# CutMonitor_Motor.net
KiCad netlist of a schematic drawn in Altium Designer
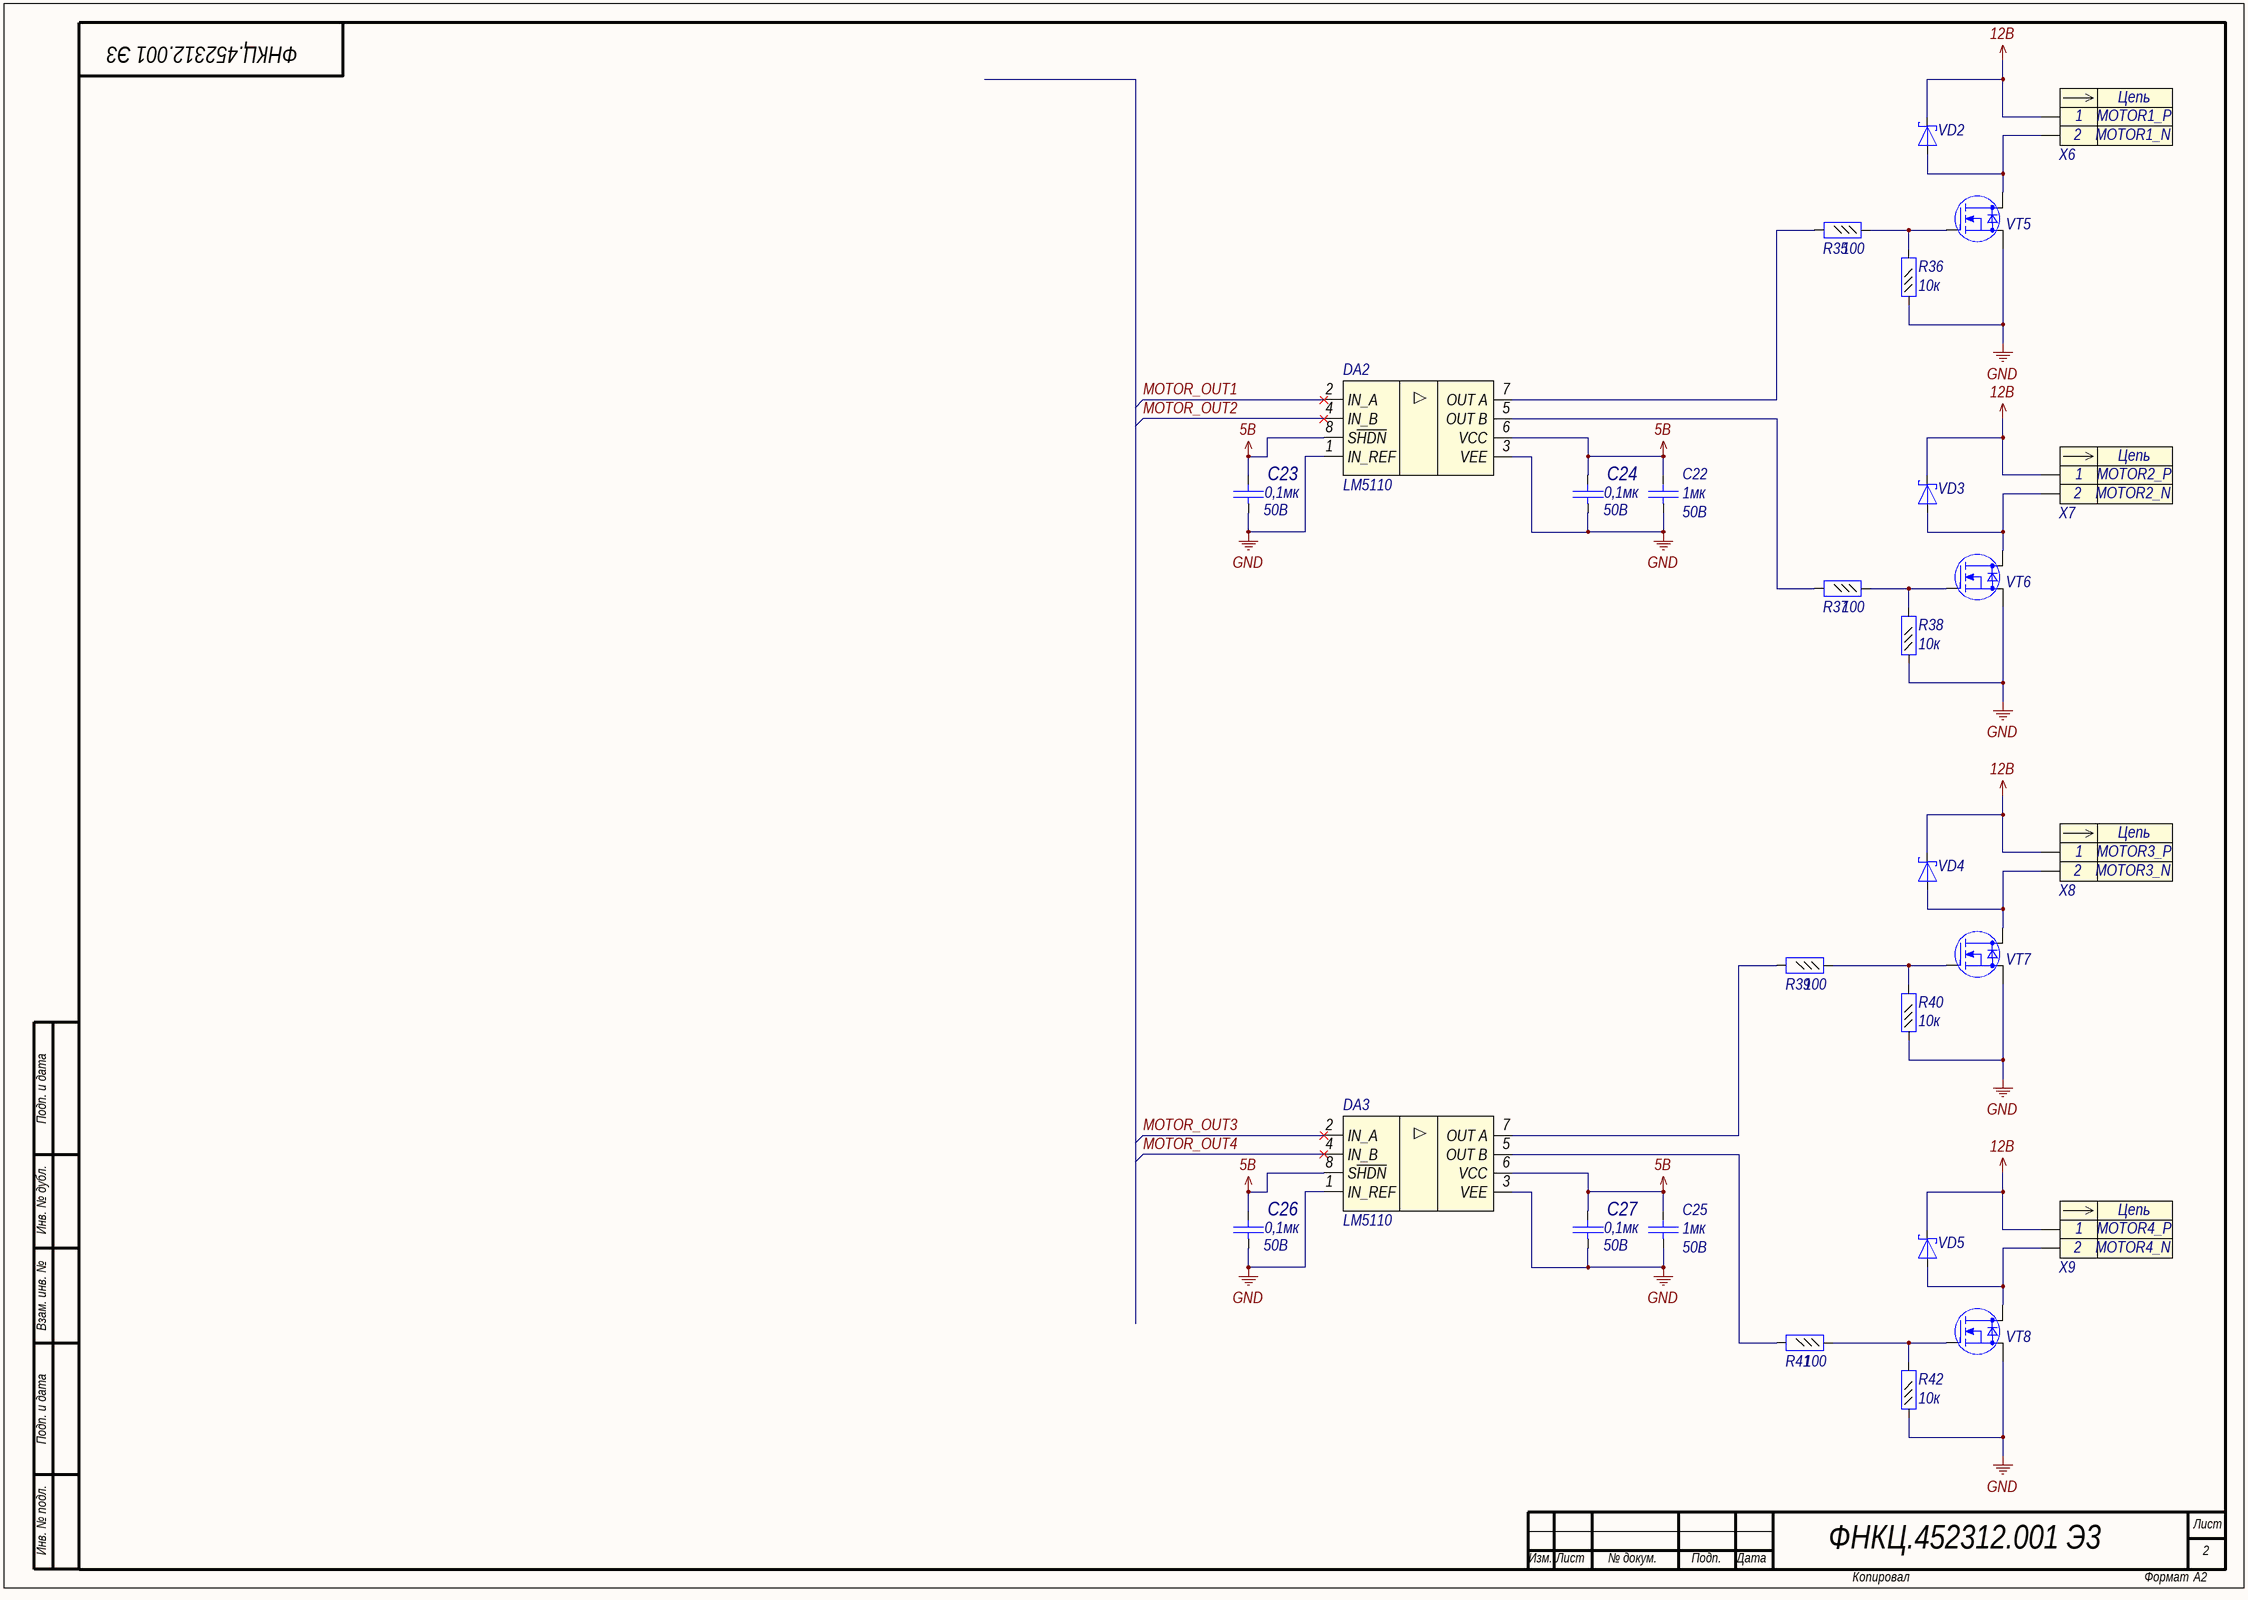
[diagram p0: CutMonitor_Motor.SchDoc]

(export (version "E")
  (design (tool "Eeschema 10.0.6"))
  (components
    (comp (ref "C22")
      (value "1мк")
      (footprint "C0805")
      (description "Конденсатор")
      (fields
        (field (name "VOLTAGE") "50B")
        (field (name "PART NUMBER") "GRM21BR71H105K")
        (field (name "Comment") "Capacitor")
      )
      (libsource (lib "MOP44") (part "Capacitor"))
    )
    (comp (ref "C23")
      (value "0,1мк")
      (footprint "C0603")
      (description "Конденсатор")
      (fields
        (field (name "VOLTAGE") "50B")
        (field (name "PART NUMBER") "GRM188R71H104KA93D")
        (field (name "Comment") "Capacitor")
      )
      (libsource (lib "MOP44") (part "Capacitor"))
    )
    (comp (ref "C24")
      (value "0,1мк")
      (footprint "C0603")
      (description "Конденсатор")
      (fields
        (field (name "VOLTAGE") "50B")
        (field (name "PART NUMBER") "GRM188R71H104KA93D")
        (field (name "Comment") "Capacitor")
      )
      (libsource (lib "MOP44") (part "Capacitor"))
    )
    (comp (ref "C25")
      (value "1мк")
      (footprint "C0805")
      (description "Конденсатор")
      (fields
        (field (name "VOLTAGE") "50B")
        (field (name "PART NUMBER") "GRM21BR71H105K")
        (field (name "Comment") "Capacitor")
      )
      (libsource (lib "MOP44") (part "Capacitor"))
    )
    (comp (ref "C26")
      (value "0,1мк")
      (footprint "C0603")
      (description "Конденсатор")
      (fields
        (field (name "VOLTAGE") "50B")
        (field (name "PART NUMBER") "GRM188R71H104KA93D")
        (field (name "Comment") "Capacitor")
      )
      (libsource (lib "MOP44") (part "Capacitor"))
    )
    (comp (ref "C27")
      (value "0,1мк")
      (footprint "C0603")
      (description "Конденсатор")
      (fields
        (field (name "VOLTAGE") "50B")
        (field (name "PART NUMBER") "GRM188R71H104KA93D")
        (field (name "Comment") "Capacitor")
      )
      (libsource (lib "MOP44") (part "Capacitor"))
    )
    (comp (ref "DA2")
      (value "LM5110")
      (footprint "SO8")
      (description "Driver 5A 2-OUT Low Side Inv/Non-Inv")
      (fields (field (name "PART NUMBER") "LM5110-1M"))
      (libsource (lib "MOP44") (part "LM5110"))
    )
    (comp (ref "DA3")
      (value "LM5110")
      (footprint "SO8")
      (description "Driver 5A 2-OUT Low Side Inv/Non-Inv")
      (fields (field (name "PART NUMBER") "LM5110-1M"))
      (libsource (lib "MOP44") (part "LM5110"))
    )
    (comp (ref "R35")
      (value "100")
      (footprint "R0603")
      (description "Резистор")
      (fields (field (name "PART NUMBER") "RC0603FR-07100RL") (field (name "POWER") "0,062Вт"))
      (libsource (lib "MOP44") (part "Resistor_0,062Вт"))
    )
    (comp (ref "R36")
      (value "10к")
      (footprint "R0603")
      (description "Резистор")
      (fields (field (name "PART NUMBER") "RC0603FR-0710KL") (field (name "POWER") "0,062Вт"))
      (libsource (lib "") (part "Resistor_0,062Вт_1"))
    )
    (comp (ref "R37")
      (value "100")
      (footprint "R0603")
      (description "Резистор")
      (fields (field (name "PART NUMBER") "RC0603FR-07100RL") (field (name "POWER") "0,062Вт"))
      (libsource (lib "MOP44") (part "Resistor_0,062Вт"))
    )
    (comp (ref "R38")
      (value "10к")
      (footprint "R0603")
      (description "Резистор")
      (fields (field (name "PART NUMBER") "RC0603FR-0710KL") (field (name "POWER") "0,062Вт"))
      (libsource (lib "") (part "Resistor_0,062Вт_1"))
    )
    (comp (ref "R39")
      (value "100")
      (footprint "R0603")
      (description "Резистор")
      (fields (field (name "PART NUMBER") "RC0603FR-07100RL") (field (name "POWER") "0,062Вт"))
      (libsource (lib "MOP44") (part "Resistor_0,062Вт"))
    )
    (comp (ref "R40")
      (value "10к")
      (footprint "R0603")
      (description "Резистор")
      (fields (field (name "PART NUMBER") "RC0603FR-0710KL") (field (name "POWER") "0,062Вт"))
      (libsource (lib "") (part "Resistor_0,062Вт_1"))
    )
    (comp (ref "R41")
      (value "100")
      (footprint "R0603")
      (description "Резистор")
      (fields (field (name "PART NUMBER") "RC0603FR-07100RL") (field (name "POWER") "0,062Вт"))
      (libsource (lib "MOP44") (part "Resistor_0,062Вт"))
    )
    (comp (ref "R42")
      (value "10к")
      (footprint "R0603")
      (description "Резистор")
      (fields (field (name "PART NUMBER") "RC0603FR-0710KL") (field (name "POWER") "0,062Вт"))
      (libsource (lib "") (part "Resistor_0,062Вт_1"))
    )
    (comp (ref "VD2")
      (value "DiodeSchottky")
      (footprint "SOD-323")
      (description "Диод Шоттки")
      (fields (field (name "PART NUMBER") "PMEG4010BEA.115"))
      (libsource (lib "MOP44") (part "DiodeSchottky"))
    )
    (comp (ref "VD3")
      (value "DiodeSchottky")
      (footprint "SOD-323")
      (description "Диод Шоттки")
      (fields (field (name "PART NUMBER") "PMEG4010BEA.115"))
      (libsource (lib "MOP44") (part "DiodeSchottky"))
    )
    (comp (ref "VD4")
      (value "DiodeSchottky")
      (footprint "SOD-323")
      (description "Диод Шоттки")
      (fields (field (name "PART NUMBER") "PMEG4010BEA.115"))
      (libsource (lib "MOP44") (part "DiodeSchottky"))
    )
    (comp (ref "VD5")
      (value "DiodeSchottky")
      (footprint "SOD-323")
      (description "Диод Шоттки")
      (fields (field (name "PART NUMBER") "PMEG4010BEA.115"))
      (libsource (lib "MOP44") (part "DiodeSchottky"))
    )
    (comp (ref "VT5")
      (value "N-MOSFET")
      (footprint "DPAK")
      (fields
        (field (name "PART NUMBER") "IRLR2905ZPBF")
        (field (name "MANUFACTURER") "International Rectifier")
      )
      (libsource (lib "MOP44") (part "N-MOSFET"))
    )
    (comp (ref "VT6")
      (value "N-MOSFET")
      (footprint "DPAK")
      (fields
        (field (name "PART NUMBER") "IRLR2905ZPBF")
        (field (name "MANUFACTURER") "International Rectifier")
      )
      (libsource (lib "MOP44") (part "N-MOSFET"))
    )
    (comp (ref "VT7")
      (value "N-MOSFET")
      (footprint "DPAK")
      (fields
        (field (name "PART NUMBER") "IRLR2905ZPBF")
        (field (name "MANUFACTURER") "International Rectifier")
      )
      (libsource (lib "MOP44") (part "N-MOSFET"))
    )
    (comp (ref "VT8")
      (value "N-MOSFET")
      (footprint "DPAK")
      (fields
        (field (name "PART NUMBER") "IRLR2905ZPBF")
        (field (name "MANUFACTURER") "International Rectifier")
      )
      (libsource (lib "MOP44") (part "N-MOSFET"))
    )
    (comp (ref "X6")
      (value "~")
      (footprint "JUMPER_2.54")
      (description "Разъем - 2 конт. вилка")
      (libsource (lib "MOP44") (part "Header_2_plg"))
    )
    (comp (ref "X7")
      (value "~")
      (footprint "JUMPER_2.54")
      (description "Разъем - 2 конт. вилка")
      (libsource (lib "MOP44") (part "Header_2_plg"))
    )
    (comp (ref "X8")
      (value "~")
      (footprint "JUMPER_2.54")
      (description "Разъем - 2 конт. вилка")
      (libsource (lib "MOP44") (part "Header_2_plg"))
    )
    (comp (ref "X9")
      (value "~")
      (footprint "JUMPER_2.54")
      (description "Разъем - 2 конт. вилка")
      (libsource (lib "MOP44") (part "Header_2_plg"))
    )
  )
  (nets
    (net (code "1") (name "/MOTOR_OUT1") (class "Default")
      (node (ref "DA2") (pin "2") (pinfunction "IN_A_2") (pintype "passive+no_connect"))
    )
    (net (code "2") (name "/MOTOR_OUT2") (class "Default")
      (node (ref "DA2") (pin "4") (pinfunction "IN_B_4") (pintype "passive+no_connect"))
    )
    (net (code "3") (name "/MOTOR_OUT3") (class "Default")
      (node (ref "DA3") (pin "2") (pinfunction "IN_A_2") (pintype "passive+no_connect"))
    )
    (net (code "4") (name "/MOTOR_OUT4") (class "Default")
      (node (ref "DA3") (pin "4") (pinfunction "IN_B_4") (pintype "passive+no_connect"))
    )
    (net (code "5") (name "5В") (class "Default")
      (node (ref "C22") (pin "2") (pinfunction "2_2") (pintype "passive"))
      (node (ref "C23") (pin "2") (pinfunction "2_2") (pintype "passive"))
      (node (ref "C24") (pin "2") (pinfunction "2_2") (pintype "passive"))
      (node (ref "C25") (pin "2") (pinfunction "2_2") (pintype "passive"))
      (node (ref "C26") (pin "2") (pinfunction "2_2") (pintype "passive"))
      (node (ref "C27") (pin "2") (pinfunction "2_2") (pintype "passive"))
      (node (ref "DA2") (pin "6") (pinfunction "VCC_6") (pintype "passive"))
      (node (ref "DA2") (pin "8") (pinfunction "S~{HDN}_8") (pintype "passive"))
      (node (ref "DA3") (pin "6") (pinfunction "VCC_6") (pintype "passive"))
      (node (ref "DA3") (pin "8") (pinfunction "S~{HDN}_8") (pintype "passive"))
    )
    (net (code "6") (name "12B") (class "Default")
      (node (ref "VD2") (pin "1") (pinfunction "K_1") (pintype "passive"))
      (node (ref "VD3") (pin "1") (pinfunction "K_1") (pintype "passive"))
      (node (ref "VD4") (pin "1") (pinfunction "K_1") (pintype "passive"))
      (node (ref "VD5") (pin "1") (pinfunction "K_1") (pintype "passive"))
      (node (ref "X6") (pin "1") (pinfunction "1_1") (pintype "passive"))
      (node (ref "X7") (pin "1") (pinfunction "1_1") (pintype "passive"))
      (node (ref "X8") (pin "1") (pinfunction "1_1") (pintype "passive"))
      (node (ref "X9") (pin "1") (pinfunction "1_1") (pintype "passive"))
    )
    (net (code "7") (name "GND") (class "Default")
      (node (ref "C22") (pin "1") (pinfunction "1_1") (pintype "passive"))
      (node (ref "C23") (pin "1") (pinfunction "1_1") (pintype "passive"))
      (node (ref "C24") (pin "1") (pinfunction "1_1") (pintype "passive"))
      (node (ref "C25") (pin "1") (pinfunction "1_1") (pintype "passive"))
      (node (ref "C26") (pin "1") (pinfunction "1_1") (pintype "passive"))
      (node (ref "C27") (pin "1") (pinfunction "1_1") (pintype "passive"))
      (node (ref "DA2") (pin "1") (pinfunction "IN_REF_1") (pintype "passive"))
      (node (ref "DA2") (pin "3") (pinfunction "VEE_3") (pintype "passive"))
      (node (ref "DA3") (pin "1") (pinfunction "IN_REF_1") (pintype "passive"))
      (node (ref "DA3") (pin "3") (pinfunction "VEE_3") (pintype "passive"))
      (node (ref "R36") (pin "1") (pinfunction "1_1") (pintype "passive"))
      (node (ref "R38") (pin "1") (pinfunction "1_1") (pintype "passive"))
      (node (ref "R40") (pin "1") (pinfunction "1_1") (pintype "passive"))
      (node (ref "R42") (pin "1") (pinfunction "1_1") (pintype "passive"))
      (node (ref "VT5") (pin "3") (pinfunction "S_3") (pintype "passive"))
      (node (ref "VT6") (pin "3") (pinfunction "S_3") (pintype "passive"))
      (node (ref "VT7") (pin "3") (pinfunction "S_3") (pintype "passive"))
      (node (ref "VT8") (pin "3") (pinfunction "S_3") (pintype "passive"))
    )
    (net (code "8") (name "Net-(DA2-OUT_A)") (class "Default")
      (node (ref "DA2") (pin "7") (pinfunction "OUT_A_7") (pintype "passive"))
      (node (ref "R35") (pin "2") (pinfunction "2_2") (pintype "passive"))
    )
    (net (code "9") (name "Net-(DA2-OUT_B)") (class "Default")
      (node (ref "DA2") (pin "5") (pinfunction "OUT_B_5") (pintype "passive"))
      (node (ref "R37") (pin "2") (pinfunction "2_2") (pintype "passive"))
    )
    (net (code "10") (name "Net-(DA3-OUT_A)") (class "Default")
      (node (ref "DA3") (pin "7") (pinfunction "OUT_A_7") (pintype "passive"))
      (node (ref "R39") (pin "2") (pinfunction "2_2") (pintype "passive"))
    )
    (net (code "11") (name "Net-(DA3-OUT_B)") (class "Default")
      (node (ref "DA3") (pin "5") (pinfunction "OUT_B_5") (pintype "passive"))
      (node (ref "R41") (pin "2") (pinfunction "2_2") (pintype "passive"))
    )
    (net (code "12") (name "Net-(VD2-A)") (class "Default")
      (node (ref "VD2") (pin "2") (pinfunction "A_2") (pintype "passive"))
      (node (ref "VT5") (pin "2") (pinfunction "D_2") (pintype "passive"))
      (node (ref "X6") (pin "2") (pinfunction "2_2") (pintype "passive"))
    )
    (net (code "13") (name "Net-(VD3-A)") (class "Default")
      (node (ref "VD3") (pin "2") (pinfunction "A_2") (pintype "passive"))
      (node (ref "VT6") (pin "2") (pinfunction "D_2") (pintype "passive"))
      (node (ref "X7") (pin "2") (pinfunction "2_2") (pintype "passive"))
    )
    (net (code "14") (name "Net-(VD4-A)") (class "Default")
      (node (ref "VD4") (pin "2") (pinfunction "A_2") (pintype "passive"))
      (node (ref "VT7") (pin "2") (pinfunction "D_2") (pintype "passive"))
      (node (ref "X8") (pin "2") (pinfunction "2_2") (pintype "passive"))
    )
    (net (code "15") (name "Net-(VD5-A)") (class "Default")
      (node (ref "VD5") (pin "2") (pinfunction "A_2") (pintype "passive"))
      (node (ref "VT8") (pin "2") (pinfunction "D_2") (pintype "passive"))
      (node (ref "X9") (pin "2") (pinfunction "2_2") (pintype "passive"))
    )
    (net (code "16") (name "Net-(VT5-G)") (class "Default")
      (node (ref "R35") (pin "1") (pinfunction "1_1") (pintype "passive"))
      (node (ref "R36") (pin "2") (pinfunction "2_2") (pintype "passive"))
      (node (ref "VT5") (pin "1") (pinfunction "G_1") (pintype "passive"))
    )
    (net (code "17") (name "Net-(VT6-G)") (class "Default")
      (node (ref "R37") (pin "1") (pinfunction "1_1") (pintype "passive"))
      (node (ref "R38") (pin "2") (pinfunction "2_2") (pintype "passive"))
      (node (ref "VT6") (pin "1") (pinfunction "G_1") (pintype "passive"))
    )
    (net (code "18") (name "Net-(VT7-G)") (class "Default")
      (node (ref "R39") (pin "1") (pinfunction "1_1") (pintype "passive"))
      (node (ref "R40") (pin "2") (pinfunction "2_2") (pintype "passive"))
      (node (ref "VT7") (pin "1") (pinfunction "G_1") (pintype "passive"))
    )
    (net (code "19") (name "Net-(VT8-G)") (class "Default")
      (node (ref "R41") (pin "1") (pinfunction "1_1") (pintype "passive"))
      (node (ref "R42") (pin "2") (pinfunction "2_2") (pintype "passive"))
      (node (ref "VT8") (pin "1") (pinfunction "G_1") (pintype "passive"))
    )
  )
)
